# Moteino-MH-z19-Shield.net
KiCad netlist of a schematic drawn in EAGLE
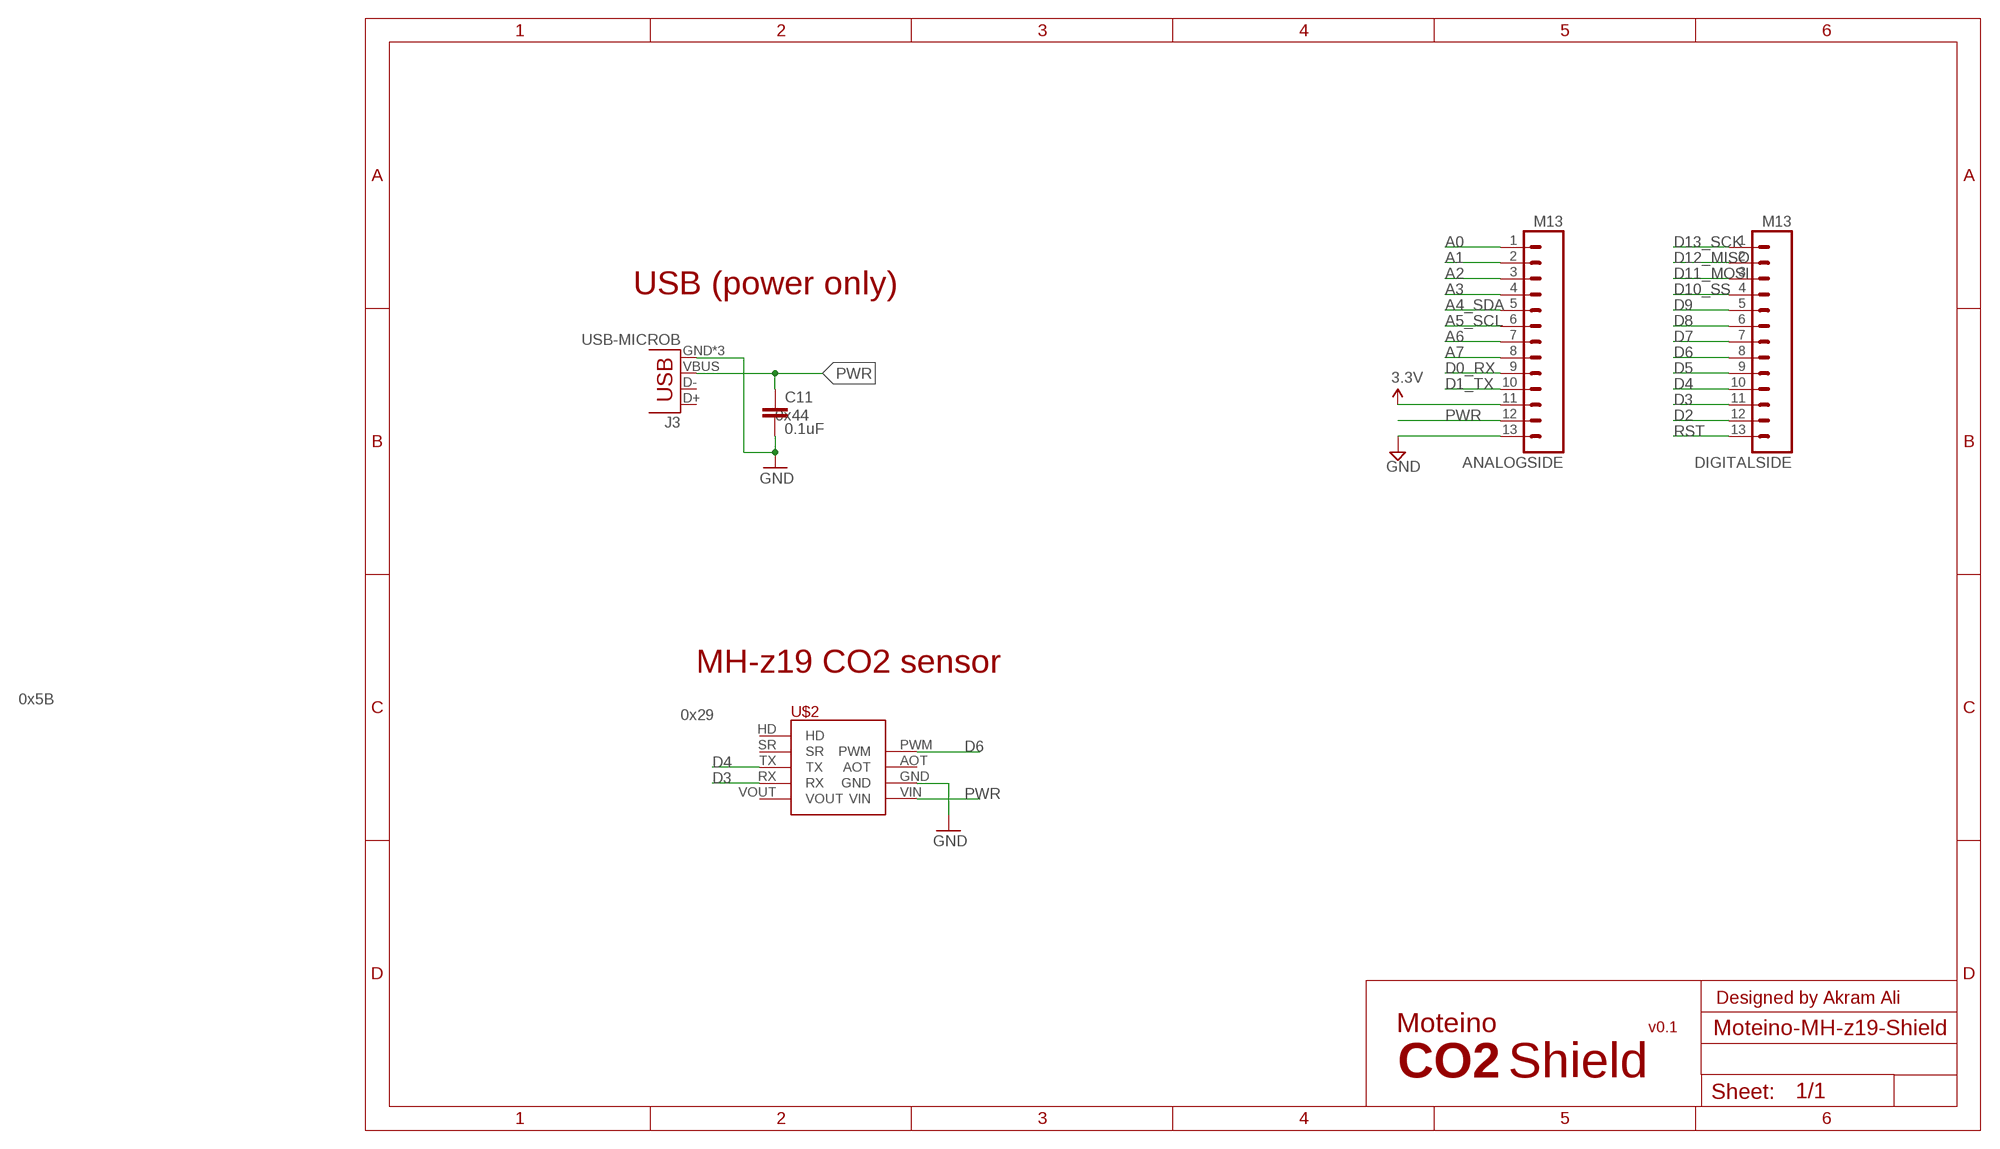
[diagram p0: schematic, sheet 1]

(export (version "E")
  (design (tool "Eeschema 10.0.6"))
  (components
    (comp (ref "ANALOGSIDE")
      (value "M13")
      (footprint "eagle-import:1X13")
      (libsource (lib "eagle-import") (part "M13"))
    )
    (comp (ref "C11")
      (value "0.1uF")
      (footprint "eagle-import:0805")
      (fields (field (name "MPN") "CC0805KRX7R9BB104"))
      (libsource (lib "eagle-import") (part "CAP0805"))
    )
    (comp (ref "DIGITALSIDE")
      (value "M13")
      (footprint "eagle-import:1X13")
      (libsource (lib "eagle-import") (part "M13"))
    )
    (comp (ref "J3")
      (value "USB-MICROB")
      (footprint "eagle-import:USB-MICROB")
      (fields (field (name "MPN") "47346-0001"))
      (libsource (lib "eagle-import") (part "USB-MICROB"))
    )
    (comp (ref "U$2")
      (value "MH-Z19")
      (footprint "eagle-import:MH-Z19")
      (libsource (lib "eagle-import") (part "MH-Z19"))
    )
  )
  (nets
    (net (code "1") (name "/A0") (class "Default")
      (node (ref "ANALOGSIDE") (pin "1") (pinfunction "1_1") (pintype "passive"))
    )
    (net (code "2") (name "/A1") (class "Default")
      (node (ref "ANALOGSIDE") (pin "2") (pinfunction "2_2") (pintype "passive"))
    )
    (net (code "3") (name "/A2") (class "Default")
      (node (ref "ANALOGSIDE") (pin "3") (pinfunction "3_3") (pintype "passive"))
    )
    (net (code "4") (name "/A3") (class "Default")
      (node (ref "ANALOGSIDE") (pin "4") (pinfunction "4_4") (pintype "passive"))
    )
    (net (code "5") (name "/A4_SDA") (class "Default")
      (node (ref "ANALOGSIDE") (pin "5") (pinfunction "5_5") (pintype "passive"))
    )
    (net (code "6") (name "/A5_SCL") (class "Default")
      (node (ref "ANALOGSIDE") (pin "6") (pinfunction "6_6") (pintype "passive"))
    )
    (net (code "7") (name "/A6") (class "Default")
      (node (ref "ANALOGSIDE") (pin "7") (pinfunction "7_7") (pintype "passive"))
    )
    (net (code "8") (name "/A7") (class "Default")
      (node (ref "ANALOGSIDE") (pin "8") (pinfunction "8_8") (pintype "passive"))
    )
    (net (code "9") (name "/D0_RX") (class "Default")
      (node (ref "ANALOGSIDE") (pin "9") (pinfunction "9_9") (pintype "passive"))
    )
    (net (code "10") (name "/D1_TX") (class "Default")
      (node (ref "ANALOGSIDE") (pin "10") (pinfunction "10_10") (pintype "passive"))
    )
    (net (code "11") (name "/D2") (class "Default")
      (node (ref "DIGITALSIDE") (pin "12") (pinfunction "12_12") (pintype "passive"))
    )
    (net (code "12") (name "/D3") (class "Default")
      (node (ref "DIGITALSIDE") (pin "11") (pinfunction "11_11") (pintype "passive"))
      (node (ref "U$2") (pin "RX") (pinfunction "RX_RX") (pintype "bidirectional"))
    )
    (net (code "13") (name "/D4") (class "Default")
      (node (ref "DIGITALSIDE") (pin "10") (pinfunction "10_10") (pintype "passive"))
      (node (ref "U$2") (pin "TX") (pinfunction "TX_TX") (pintype "bidirectional"))
    )
    (net (code "14") (name "/D5") (class "Default")
      (node (ref "DIGITALSIDE") (pin "9") (pinfunction "9_9") (pintype "passive"))
    )
    (net (code "15") (name "/D6") (class "Default")
      (node (ref "DIGITALSIDE") (pin "8") (pinfunction "8_8") (pintype "passive"))
      (node (ref "U$2") (pin "PWM") (pinfunction "PWM_PWM") (pintype "bidirectional"))
    )
    (net (code "16") (name "/D7") (class "Default")
      (node (ref "DIGITALSIDE") (pin "7") (pinfunction "7_7") (pintype "passive"))
    )
    (net (code "17") (name "/D8") (class "Default")
      (node (ref "DIGITALSIDE") (pin "6") (pinfunction "6_6") (pintype "passive"))
    )
    (net (code "18") (name "/D9") (class "Default")
      (node (ref "DIGITALSIDE") (pin "5") (pinfunction "5_5") (pintype "passive"))
    )
    (net (code "19") (name "/D10_SS") (class "Default")
      (node (ref "DIGITALSIDE") (pin "4") (pinfunction "4_4") (pintype "passive"))
    )
    (net (code "20") (name "/D11_MOSI") (class "Default")
      (node (ref "DIGITALSIDE") (pin "3") (pinfunction "3_3") (pintype "passive"))
    )
    (net (code "21") (name "/D12_MISO") (class "Default")
      (node (ref "DIGITALSIDE") (pin "2") (pinfunction "2_2") (pintype "passive"))
    )
    (net (code "22") (name "/D13_SCK") (class "Default")
      (node (ref "DIGITALSIDE") (pin "1") (pinfunction "1_1") (pintype "passive"))
    )
    (net (code "23") (name "/RST") (class "Default")
      (node (ref "DIGITALSIDE") (pin "13") (pinfunction "13_13") (pintype "passive"))
    )
    (net (code "24") (name "3.3V") (class "Default")
      (node (ref "ANALOGSIDE") (pin "11") (pinfunction "11_11") (pintype "passive"))
    )
    (net (code "25") (name "GND") (class "Default")
      (node (ref "ANALOGSIDE") (pin "13") (pinfunction "13_13") (pintype "passive"))
      (node (ref "C11") (pin "2") (pinfunction "2_2") (pintype "passive"))
      (node (ref "J3") (pin "GND") (pinfunction "GND_GND") (pintype "bidirectional"))
      (node (ref "J3") (pin "MT1") (pinfunction "GND_MT1") (pintype "bidirectional"))
      (node (ref "J3") (pin "MT2") (pinfunction "GND_MT2") (pintype "bidirectional"))
      (node (ref "U$2") (pin "GND") (pinfunction "GND_GND") (pintype "bidirectional"))
    )
    (net (code "26") (name "PWR") (class "Default")
      (node (ref "ANALOGSIDE") (pin "12") (pinfunction "12_12") (pintype "passive"))
      (node (ref "C11") (pin "1") (pinfunction "1_1") (pintype "passive"))
      (node (ref "J3") (pin "VBUS") (pinfunction "VBUS_VBUS") (pintype "bidirectional"))
      (node (ref "U$2") (pin "VIN") (pinfunction "VIN_VIN") (pintype "bidirectional"))
    )
    (net (code "27") (name "unconnected-(J3-PadD+)") (class "Default")
      (node (ref "J3") (pin "D+") (pinfunction "D+_D+") (pintype "bidirectional"))
    )
    (net (code "28") (name "unconnected-(J3-PadD-)") (class "Default")
      (node (ref "J3") (pin "D-") (pinfunction "D-_D-") (pintype "bidirectional"))
    )
    (net (code "29") (name "unconnected-(U$2-PadAOT)") (class "Default")
      (node (ref "U$2") (pin "AOT") (pinfunction "AOT_AOT") (pintype "bidirectional"))
    )
    (net (code "30") (name "unconnected-(U$2-PadHD)") (class "Default")
      (node (ref "U$2") (pin "HD") (pinfunction "HD_HD") (pintype "bidirectional"))
    )
    (net (code "31") (name "unconnected-(U$2-PadSR)") (class "Default")
      (node (ref "U$2") (pin "SR") (pinfunction "SR_SR") (pintype "bidirectional"))
    )
    (net (code "32") (name "unconnected-(U$2-PadVOUT)") (class "Default")
      (node (ref "U$2") (pin "VOUT") (pinfunction "VOUT_VOUT") (pintype "bidirectional"))
    )
  )
)
